# ADF4351_Teensy.net
KiCad netlist of a schematic drawn in EAGLE
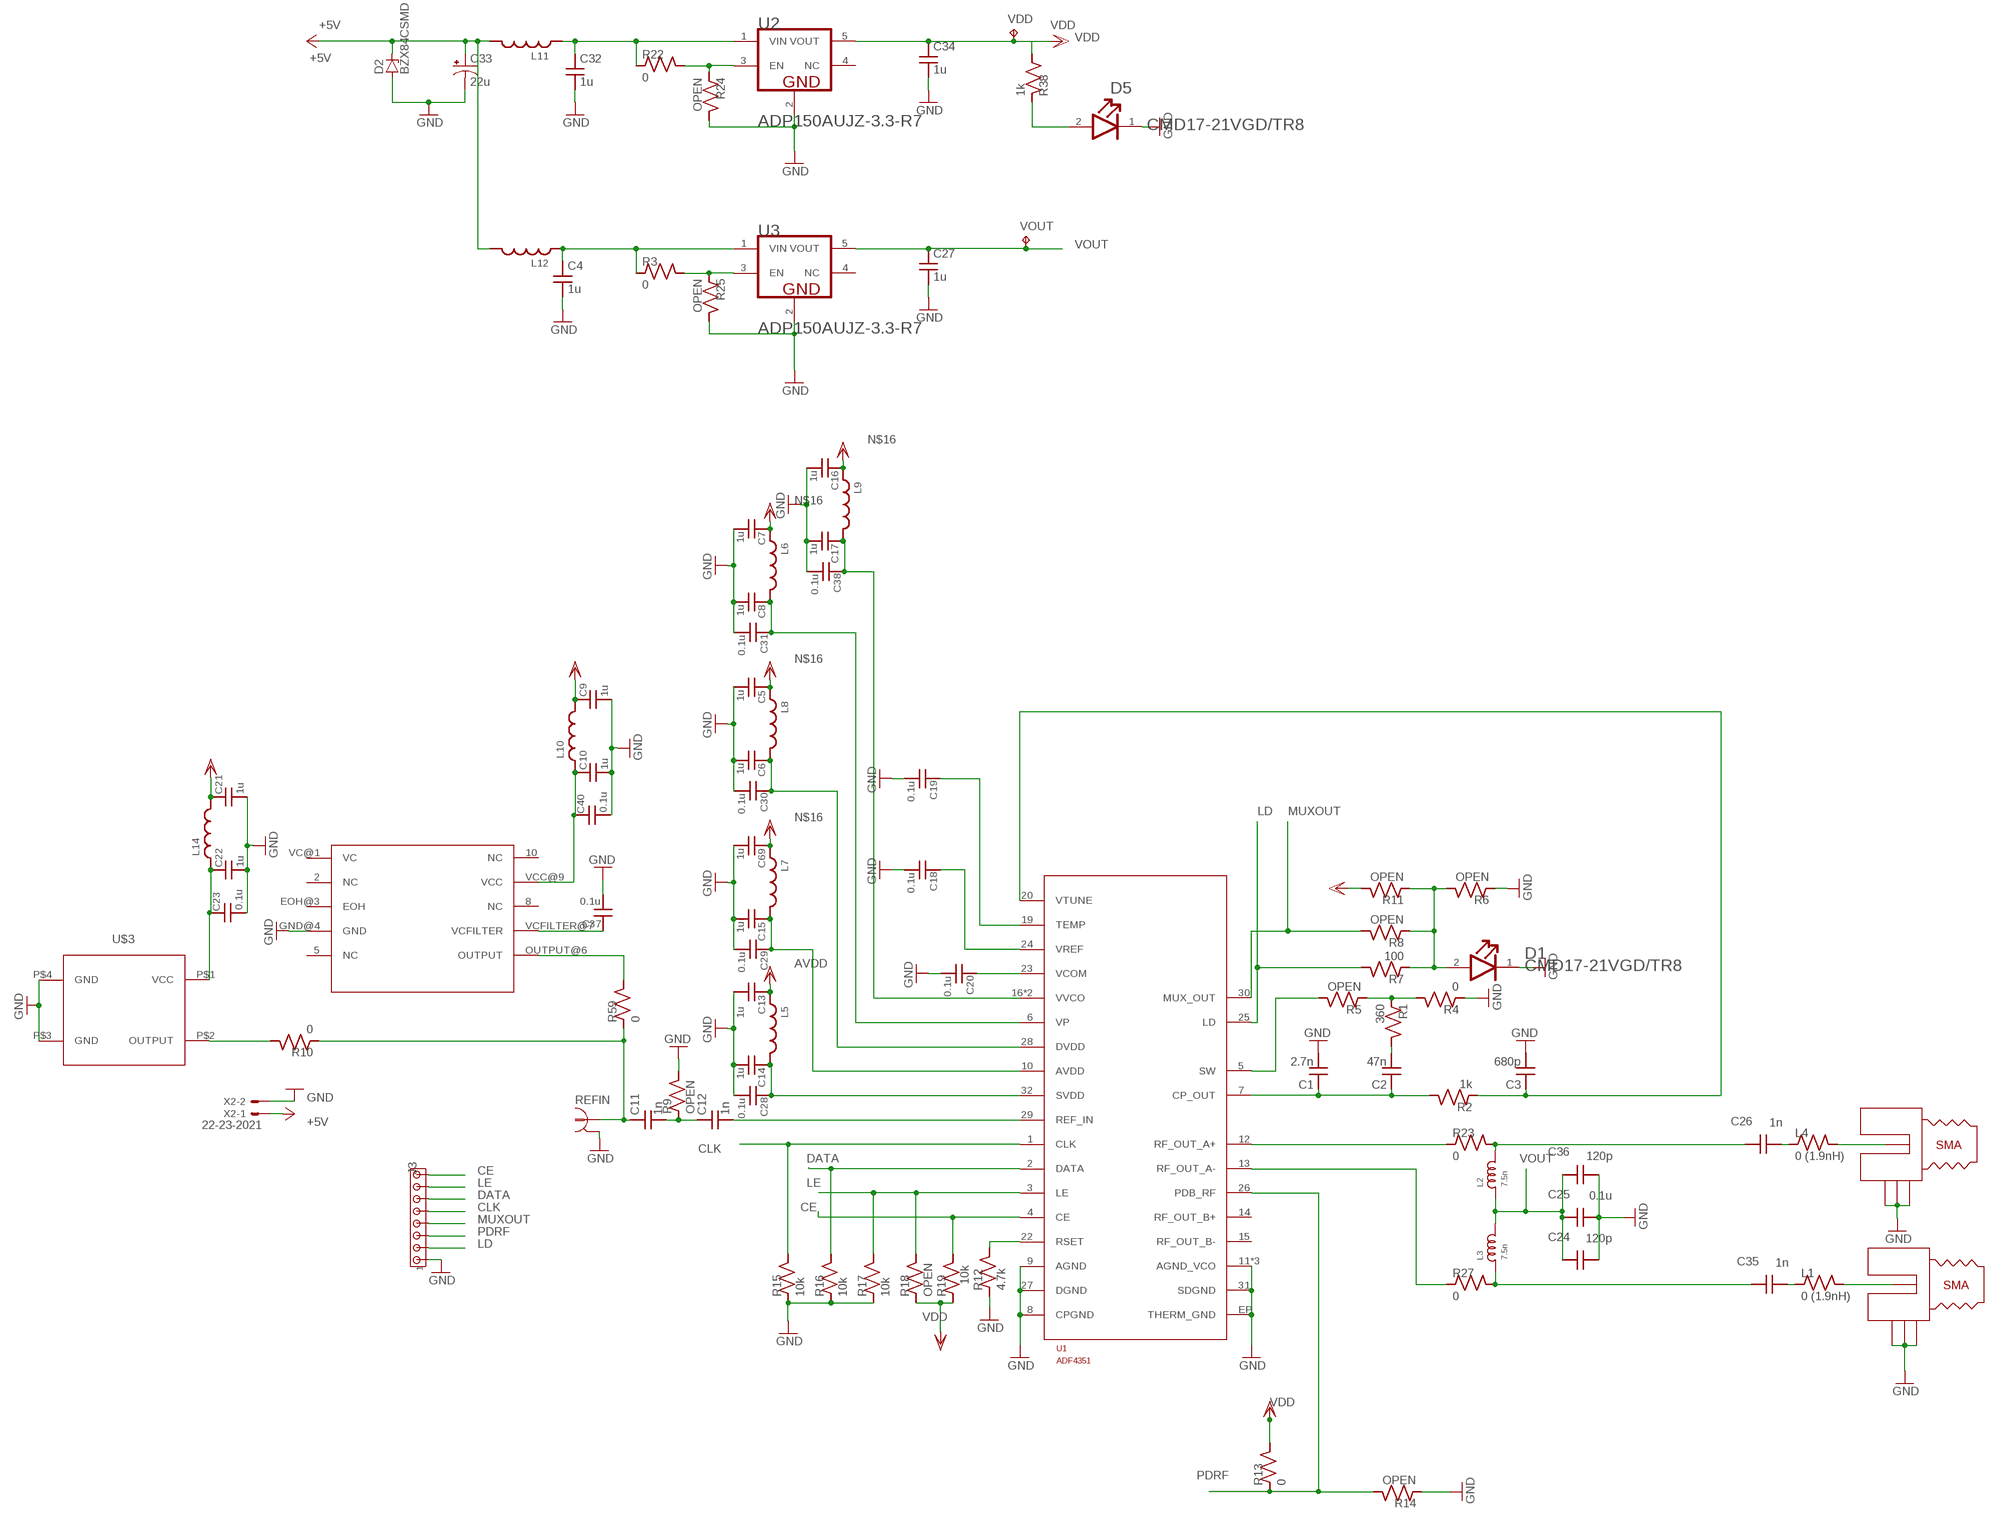
[diagram p0: schematic, sheet 1, part 1 of 2]
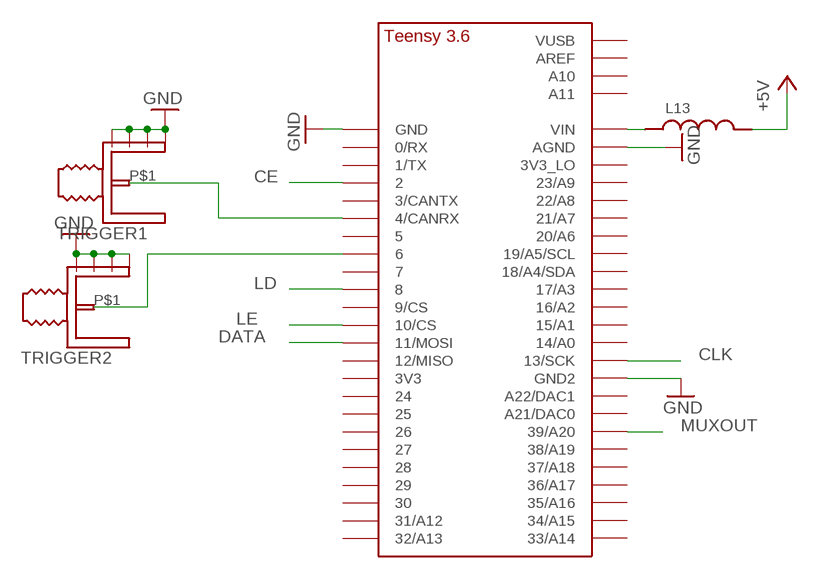
[diagram p1: schematic, sheet 1, part 2 of 2]

(export (version "E")
  (design (tool "Eeschema 10.0.6"))
  (components
    (comp (ref "535L250X2GT5")
      (value "535L250X2GT5")
      (footprint "eagle-import:535L250X2GT5")
      (libsource (lib "eagle-import") (part "535L250X2GT5"))
    )
    (comp (ref "C1")
      (value "2.7n")
      (footprint "eagle-import:C_MLCC_0603")
      (fields
        (field (name "DIGIKEY_PART_NUMBER") "1276-2022-1-ND")
        (field (name "PART_NUMBER") "CL10B272KB8NNNC")
      )
      (libsource (lib "eagle-import") (part "C_MLCC_SMDCMLCC_0603"))
    )
    (comp (ref "C2")
      (value "47n")
      (footprint "eagle-import:C_MLCC_0603")
      (fields
        (field (name "DIGIKEY_PART_NUMBER") "1276-2070-1-ND")
        (field (name "PART_NUMBER") "CL10B473JB8NNNC")
      )
      (libsource (lib "eagle-import") (part "C_MLCC_SMDCMLCC_0603"))
    )
    (comp (ref "C3")
      (value "680p")
      (footprint "eagle-import:C_MLCC_0603")
      (fields
        (field (name "DIGIKEY_PART_NUMBER") "1276-2327-1-ND")
        (field (name "PART_NUMBER") "CL10C681FB8NNNC")
      )
      (libsource (lib "eagle-import") (part "C_MLCC_SMDCMLCC_0603"))
    )
    (comp (ref "C4")
      (value "1u")
      (footprint "eagle-import:C_MLCC_0603")
      (fields
        (field (name "DIGIKEY_PART_NUMBER") "1276-1019-1-ND")
        (field (name "PART_NUMBER") "CL10B105KO8NNNC")
      )
      (libsource (lib "eagle-import") (part "C_MLCC_SMDCMLCC_0603"))
    )
    (comp (ref "C5")
      (value "1u")
      (footprint "eagle-import:C_MLCC_0306")
      (fields
        (field (name "DIGIKEY_PART_NUMBER") "445-13750-1-ND")
        (field (name "PART_NUMBER") "C0816X5R1C105M050AC")
      )
      (libsource (lib "eagle-import") (part "C_MLCC_SMDCMLCC_0306"))
    )
    (comp (ref "C6")
      (value "1u")
      (footprint "eagle-import:C_MLCC_0306")
      (fields
        (field (name "DIGIKEY_PART_NUMBER") "445-13750-1-ND")
        (field (name "PART_NUMBER") "C0816X5R1C105M050AC")
      )
      (libsource (lib "eagle-import") (part "C_MLCC_SMDCMLCC_0306"))
    )
    (comp (ref "C7")
      (value "1u")
      (footprint "eagle-import:C_MLCC_0306")
      (fields
        (field (name "DIGIKEY_PART_NUMBER") "445-13750-1-ND")
        (field (name "PART_NUMBER") "C0816X5R1C105M050AC")
      )
      (libsource (lib "eagle-import") (part "C_MLCC_SMDCMLCC_0306"))
    )
    (comp (ref "C8")
      (value "1u")
      (footprint "eagle-import:C_MLCC_0306")
      (fields
        (field (name "DIGIKEY_PART_NUMBER") "445-13750-1-ND")
        (field (name "PART_NUMBER") "C0816X5R1C105M050AC")
      )
      (libsource (lib "eagle-import") (part "C_MLCC_SMDCMLCC_0306"))
    )
    (comp (ref "C9")
      (value "1u")
      (footprint "eagle-import:C_MLCC_0306")
      (fields
        (field (name "DIGIKEY_PART_NUMBER") "445-13750-1-ND")
        (field (name "PART_NUMBER") "C0816X5R1C105M050AC")
      )
      (libsource (lib "eagle-import") (part "C_MLCC_SMDCMLCC_0306"))
    )
    (comp (ref "C10")
      (value "1u")
      (footprint "eagle-import:C_MLCC_0306")
      (fields
        (field (name "DIGIKEY_PART_NUMBER") "445-13750-1-ND")
        (field (name "PART_NUMBER") "C0816X5R1C105M050AC")
      )
      (libsource (lib "eagle-import") (part "C_MLCC_SMDCMLCC_0306"))
    )
    (comp (ref "C11")
      (value "1n")
      (footprint "eagle-import:C_MLCC_0603")
      (fields
        (field (name "DIGIKEY_PART_NUMBER") "1276-1091-1-ND")
        (field (name "PART_NUMBER") "CL10C102JB8NNNC")
      )
      (libsource (lib "eagle-import") (part "C_MLCC_SMDCMLCC_0603"))
    )
    (comp (ref "C12")
      (value "1n")
      (footprint "eagle-import:C_MLCC_0603")
      (fields
        (field (name "DIGIKEY_PART_NUMBER") "1276-1091-1-ND")
        (field (name "PART_NUMBER") "CL10C102JB8NNNC")
      )
      (libsource (lib "eagle-import") (part "C_MLCC_SMDCMLCC_0603"))
    )
    (comp (ref "C13")
      (value "1u")
      (footprint "eagle-import:C_MLCC_0306")
      (fields
        (field (name "DIGIKEY_PART_NUMBER") "445-13750-1-ND")
        (field (name "PART_NUMBER") "C0816X5R1C105M050AC")
      )
      (libsource (lib "eagle-import") (part "C_MLCC_SMDCMLCC_0306"))
    )
    (comp (ref "C14")
      (value "1u")
      (footprint "eagle-import:C_MLCC_0306")
      (fields
        (field (name "DIGIKEY_PART_NUMBER") "445-13750-1-ND")
        (field (name "PART_NUMBER") "C0816X5R1C105M050AC")
      )
      (libsource (lib "eagle-import") (part "C_MLCC_SMDCMLCC_0306"))
    )
    (comp (ref "C15")
      (value "1u")
      (footprint "eagle-import:C_MLCC_0306")
      (fields
        (field (name "DIGIKEY_PART_NUMBER") "445-13750-1-ND")
        (field (name "PART_NUMBER") "C0816X5R1C105M050AC")
      )
      (libsource (lib "eagle-import") (part "C_MLCC_SMDCMLCC_0306"))
    )
    (comp (ref "C16")
      (value "1u")
      (footprint "eagle-import:C_MLCC_0306")
      (fields
        (field (name "DIGIKEY_PART_NUMBER") "445-13750-1-ND")
        (field (name "PART_NUMBER") "C0816X5R1C105M050AC")
      )
      (libsource (lib "eagle-import") (part "C_MLCC_SMDCMLCC_0306"))
    )
    (comp (ref "C17")
      (value "1u")
      (footprint "eagle-import:C_MLCC_0306")
      (fields
        (field (name "DIGIKEY_PART_NUMBER") "445-13750-1-ND")
        (field (name "PART_NUMBER") "C0816X5R1C105M050AC")
      )
      (libsource (lib "eagle-import") (part "C_MLCC_SMDCMLCC_0306"))
    )
    (comp (ref "C18")
      (value "0.1u")
      (footprint "eagle-import:C_MLCC_0204")
      (fields
        (field (name "DIGIKEY_PART_NUMBER") "587-5137-1-ND")
        (field (name "PART_NUMBER") "LWK105C7104MP-F")
      )
      (libsource (lib "eagle-import") (part "C_MLCC_SMDCMLCC_0204"))
    )
    (comp (ref "C19")
      (value "0.1u")
      (footprint "eagle-import:C_MLCC_0204")
      (fields
        (field (name "DIGIKEY_PART_NUMBER") "587-5137-1-ND")
        (field (name "PART_NUMBER") "LWK105C7104MP-F")
      )
      (libsource (lib "eagle-import") (part "C_MLCC_SMDCMLCC_0204"))
    )
    (comp (ref "C20")
      (value "0.1u")
      (footprint "eagle-import:C_MLCC_0204")
      (fields
        (field (name "DIGIKEY_PART_NUMBER") "587-5137-1-ND")
        (field (name "PART_NUMBER") "LWK105C7104MP-F")
      )
      (libsource (lib "eagle-import") (part "C_MLCC_SMDCMLCC_0204"))
    )
    (comp (ref "C21")
      (value "1u")
      (footprint "eagle-import:C_MLCC_0306")
      (fields
        (field (name "DIGIKEY_PART_NUMBER") "445-13750-1-ND")
        (field (name "PART_NUMBER") "C0816X5R1C105M050AC")
      )
      (libsource (lib "eagle-import") (part "C_MLCC_SMDCMLCC_0306"))
    )
    (comp (ref "C22")
      (value "1u")
      (footprint "eagle-import:C_MLCC_0306")
      (fields
        (field (name "DIGIKEY_PART_NUMBER") "445-13750-1-ND")
        (field (name "PART_NUMBER") "C0816X5R1C105M050AC")
      )
      (libsource (lib "eagle-import") (part "C_MLCC_SMDCMLCC_0306"))
    )
    (comp (ref "C23")
      (value "0.1u")
      (footprint "eagle-import:C_MLCC_0204")
      (fields
        (field (name "DIGIKEY_PART_NUMBER") "587-5137-1-ND")
        (field (name "PART_NUMBER") "LWK105C7104MP-F")
      )
      (libsource (lib "eagle-import") (part "C_MLCC_SMDCMLCC_0204"))
    )
    (comp (ref "C24")
      (value "120p")
      (footprint "eagle-import:C_MLCC_0402")
      (fields
        (field (name "DIGIKEY_PART_NUMBER") "587-3738-1-ND")
        (field (name "PART_NUMBER") "UMK105CG121JVHF")
      )
      (libsource (lib "eagle-import") (part "C_MLCC_SMDCMLCC_0402"))
    )
    (comp (ref "C25")
      (value "0.1u")
      (footprint "eagle-import:C_MLCC_0402")
      (fields
        (field (name "DIGIKEY_PART_NUMBER") "587-1451-1-ND")
        (field (name "PART_NUMBER") "EMK105B7104KV-F")
      )
      (libsource (lib "eagle-import") (part "C_MLCC_SMDCMLCC_0402"))
    )
    (comp (ref "C26")
      (value "1n")
      (footprint "eagle-import:C_MLCC_0402")
      (fields
        (field (name "DIGIKEY_PART_NUMBER") "1276-1635-1-ND")
        (field (name "PART_NUMBER") "CL05C102JB5NNNC")
      )
      (libsource (lib "eagle-import") (part "C_MLCC_SMDCMLCC_0402"))
    )
    (comp (ref "C27")
      (value "1u")
      (footprint "eagle-import:C_MLCC_0603")
      (fields
        (field (name "DIGIKEY_PART_NUMBER") "1276-1019-1-ND")
        (field (name "PART_NUMBER") "CL10B105KO8NNNC")
      )
      (libsource (lib "eagle-import") (part "C_MLCC_SMDCMLCC_0603"))
    )
    (comp (ref "C28")
      (value "0.1u")
      (footprint "eagle-import:C_MLCC_0204")
      (fields
        (field (name "DIGIKEY_PART_NUMBER") "587-5137-1-ND")
        (field (name "PART_NUMBER") "LWK105C7104MP-F")
      )
      (libsource (lib "eagle-import") (part "C_MLCC_SMDCMLCC_0204"))
    )
    (comp (ref "C29")
      (value "0.1u")
      (footprint "eagle-import:C_MLCC_0204")
      (fields
        (field (name "DIGIKEY_PART_NUMBER") "587-5137-1-ND")
        (field (name "PART_NUMBER") "LWK105C7104MP-F")
      )
      (libsource (lib "eagle-import") (part "C_MLCC_SMDCMLCC_0204"))
    )
    (comp (ref "C30")
      (value "0.1u")
      (footprint "eagle-import:C_MLCC_0204")
      (fields
        (field (name "DIGIKEY_PART_NUMBER") "587-5137-1-ND")
        (field (name "PART_NUMBER") "LWK105C7104MP-F")
      )
      (libsource (lib "eagle-import") (part "C_MLCC_SMDCMLCC_0204"))
    )
    (comp (ref "C31")
      (value "0.1u")
      (footprint "eagle-import:C_MLCC_0204")
      (fields
        (field (name "DIGIKEY_PART_NUMBER") "587-5137-1-ND")
        (field (name "PART_NUMBER") "LWK105C7104MP-F")
      )
      (libsource (lib "eagle-import") (part "C_MLCC_SMDCMLCC_0204"))
    )
    (comp (ref "C32")
      (value "1u")
      (footprint "eagle-import:C_MLCC_0603")
      (fields
        (field (name "DIGIKEY_PART_NUMBER") "1276-1019-1-ND")
        (field (name "PART_NUMBER") "CL10B105KO8NNNC")
      )
      (libsource (lib "eagle-import") (part "C_MLCC_SMDCMLCC_0603"))
    )
    (comp (ref "C33")
      (value "22u")
      (footprint "eagle-import:CT7343")
      (fields
        (field (name "DIGIKEY_PART_NUMBER") "478-3923-1-ND")
        (field (name "PART_NUMBER") "TAJD226K020RNJ")
      )
      (libsource (lib "eagle-import") (part "CPOL-USCT7343"))
    )
    (comp (ref "C34")
      (value "1u")
      (footprint "eagle-import:C_MLCC_0603")
      (fields
        (field (name "DIGIKEY_PART_NUMBER") "1276-1019-1-ND")
        (field (name "PART_NUMBER") "CL10B105KO8NNNC")
      )
      (libsource (lib "eagle-import") (part "C_MLCC_SMDCMLCC_0603"))
    )
    (comp (ref "C35")
      (value "1n")
      (footprint "eagle-import:C_MLCC_0402")
      (fields
        (field (name "DIGIKEY_PART_NUMBER") "1276-1635-1-ND")
        (field (name "PART_NUMBER") "CL05C102JB5NNNC")
      )
      (libsource (lib "eagle-import") (part "C_MLCC_SMDCMLCC_0402"))
    )
    (comp (ref "C36")
      (value "120p")
      (footprint "eagle-import:C_MLCC_0402")
      (fields
        (field (name "DIGIKEY_PART_NUMBER") "587-3738-1-ND")
        (field (name "PART_NUMBER") "UMK105CG121JVHF")
      )
      (libsource (lib "eagle-import") (part "C_MLCC_SMDCMLCC_0402"))
    )
    (comp (ref "C37")
      (value "0.1u")
      (footprint "eagle-import:C_MLCC_0204")
      (fields
        (field (name "DIGIKEY_PART_NUMBER") "587-5137-1-ND")
        (field (name "PART_NUMBER") "LWK105C7104MP-F")
      )
      (libsource (lib "eagle-import") (part "C_MLCC_SMDCMLCC_0204"))
    )
    (comp (ref "C38")
      (value "0.1u")
      (footprint "eagle-import:C_MLCC_0204")
      (fields
        (field (name "DIGIKEY_PART_NUMBER") "587-5137-1-ND")
        (field (name "PART_NUMBER") "LWK105C7104MP-F")
      )
      (libsource (lib "eagle-import") (part "C_MLCC_SMDCMLCC_0204"))
    )
    (comp (ref "C40")
      (value "0.1u")
      (footprint "eagle-import:C_MLCC_0204")
      (fields
        (field (name "DIGIKEY_PART_NUMBER") "587-5137-1-ND")
        (field (name "PART_NUMBER") "LWK105C7104MP-F")
      )
      (libsource (lib "eagle-import") (part "C_MLCC_SMDCMLCC_0204"))
    )
    (comp (ref "C69")
      (value "1u")
      (footprint "eagle-import:C_MLCC_0306")
      (fields
        (field (name "DIGIKEY_PART_NUMBER") "445-13750-1-ND")
        (field (name "PART_NUMBER") "C0816X5R1C105M050AC")
      )
      (libsource (lib "eagle-import") (part "C_MLCC_SMDCMLCC_0306"))
    )
    (comp (ref "D1")
      (value "VISUAL_COMMUNICATIONS_CMD17-21VGD-TR8VISUAL_COMMUNICATIONS_CMD17-21VGD-TR8_0_0")
      (footprint "eagle-import:VISUAL_COMMUNICATIONS_CMD17-21VGD-TR8_0")
      (fields
        (field (name "DIGIKEY_PART_NUMBER") "L62505CT-ND")
        (field (name "MF") "Visual Communications")
        (field (name "MOUSER_PART_NUMBER") "606-CMD17-21VGD")
      )
      (libsource (lib "eagle-import") (part "VISUAL_COMMUNICATIONS_CMD17-21VGD-TR8VISUAL_COMMUNICATIONS_CMD17-21VGD-TR8_0_0"))
    )
    (comp (ref "D2")
      (value "BZX84CSMD")
      (footprint "eagle-import:TO236")
      (fields
        (field (name "DIGIKEY_PART_NUMBER") "1727-2942-1-ND")
        (field (name "PART_NUMBER") "BZX84-C6V8,215")
      )
      (libsource (lib "eagle-import") (part "BZX84CSMD"))
    )
    (comp (ref "D5")
      (value "VISUAL_COMMUNICATIONS_CMD17-21VGD-TR8VISUAL_COMMUNICATIONS_CMD17-21VGD-TR8_0_0")
      (footprint "eagle-import:VISUAL_COMMUNICATIONS_CMD17-21VGD-TR8_0")
      (fields
        (field (name "DIGIKEY_PART_NUMBER") "L62505CT-ND")
        (field (name "MF") "Visual Communications")
        (field (name "MOUSER_PART_NUMBER") "606-CMD17-21VGD")
        (field (name "DIGIKEY_PART_NUMBER_1") "L62501CT-ND")
        (field (name "MFG_PACKAGE_IDENT") "CMD17-21VRD/TR8")
        (field (name "MPN") "CMD17-21VRD/TR8")
      )
      (libsource (lib "eagle-import") (part "VISUAL_COMMUNICATIONS_CMD17-21VGD-TR8VISUAL_COMMUNICATIONS_CMD17-21VGD-TR8_0_0"))
    )
    (comp (ref "J1")
      (value "QKDLAB_JOSH_MECHANICAL_JOHNSON_SMA_18GHZ_142-0761-891")
      (footprint "eagle-import:QKDLAB_JOSH_MECHANICAL_JOHNSON_SMA_18GHZ_4-LAYER_142-0761-891")
      (fields (field (name "DIGIKEY_PART_NUMBER") "J802-ND") (field (name "PART_NUMBER") "142-0761-891"))
      (libsource (lib "eagle-import") (part "QKDLAB_JOSH_MECHANICAL_JOHNSON_SMA_18GHZ_142-0761-891"))
    )
    (comp (ref "J2")
      (value "QKDLAB_JOSH_MECHANICAL_JOHNSON_SMA_18GHZ_142-0761-891")
      (footprint "eagle-import:QKDLAB_JOSH_MECHANICAL_JOHNSON_SMA_18GHZ_4-LAYER_142-0761-891")
      (fields (field (name "DIGIKEY_PART_NUMBER") "J802-ND") (field (name "PART_NUMBER") "142-0761-891"))
      (libsource (lib "eagle-import") (part "QKDLAB_JOSH_MECHANICAL_JOHNSON_SMA_18GHZ_142-0761-891"))
    )
    (comp (ref "J3")
      (value "MTA08-100")
      (footprint "eagle-import:10X08MTA")
      (libsource (lib "eagle-import") (part "MTA08-100"))
    )
    (comp (ref "L1")
      (value "0 (1.9nH)")
      (footprint "eagle-import:R_0402")
      (fields
        (field (name "DIGIKEY_PART_NUMBER") "541-1887-1-ND")
        (field (name "PART_NUMBER") "RCG04020000Z0ED")
      )
      (libsource (lib "eagle-import") (part "R_SMDR0402"))
    )
    (comp (ref "L2")
      (value "7.5n")
      (footprint "eagle-import:0402")
      (fields
        (field (name "DIGIKEY_PART_NUMBER") "A102558CT-ND")
        (field (name "PART_NUMBER") "36501E7N5JTDG")
      )
      (libsource (lib "eagle-import") (part "INDUCTOR-0402"))
    )
    (comp (ref "L3")
      (value "7.5n")
      (footprint "eagle-import:0402")
      (fields
        (field (name "DIGIKEY_PART_NUMBER") "A102558CT-ND")
        (field (name "PART_NUMBER") "36501E7N5JTDG")
      )
      (libsource (lib "eagle-import") (part "INDUCTOR-0402"))
    )
    (comp (ref "L4")
      (value "0 (1.9nH)")
      (footprint "eagle-import:R_0402")
      (fields
        (field (name "DIGIKEY_PART_NUMBER") "541-1887-1-ND")
        (field (name "PART_NUMBER") "RCG04020000Z0ED")
      )
      (libsource (lib "eagle-import") (part "R_SMDR0402"))
    )
    (comp (ref "L5")
      (value "L_FERRITE_SMDLFERRITE_0603")
      (footprint "eagle-import:L_FERRITE_0603")
      (fields
        (field (name "DIGIKEY_PART_NUMBER") "490-17350-1-ND")
        (field (name "PART_NUMBER") "BLM18KG102SZ1D")
      )
      (libsource (lib "eagle-import") (part "L_FERRITE_SMDLFERRITE_0603"))
    )
    (comp (ref "L6")
      (value "L_FERRITE_SMDLFERRITE_0603")
      (footprint "eagle-import:L_FERRITE_0603")
      (fields
        (field (name "DIGIKEY_PART_NUMBER") "490-17350-1-ND")
        (field (name "PART_NUMBER") "BLM18KG102SZ1D")
      )
      (libsource (lib "eagle-import") (part "L_FERRITE_SMDLFERRITE_0603"))
    )
    (comp (ref "L7")
      (value "L_FERRITE_SMDLFERRITE_0603")
      (footprint "eagle-import:L_FERRITE_0603")
      (fields
        (field (name "DIGIKEY_PART_NUMBER") "490-17350-1-ND")
        (field (name "PART_NUMBER") "BLM18KG102SZ1D")
      )
      (libsource (lib "eagle-import") (part "L_FERRITE_SMDLFERRITE_0603"))
    )
    (comp (ref "L8")
      (value "L_FERRITE_SMDLFERRITE_0603")
      (footprint "eagle-import:L_FERRITE_0603")
      (fields
        (field (name "DIGIKEY_PART_NUMBER") "490-17350-1-ND")
        (field (name "PART_NUMBER") "BLM18KG102SZ1D")
      )
      (libsource (lib "eagle-import") (part "L_FERRITE_SMDLFERRITE_0603"))
    )
    (comp (ref "L9")
      (value "L_FERRITE_SMDLFERRITE_0603")
      (footprint "eagle-import:L_FERRITE_0603")
      (fields
        (field (name "DIGIKEY_PART_NUMBER") "490-17350-1-ND")
        (field (name "PART_NUMBER") "BLM18KG102SZ1D")
      )
      (libsource (lib "eagle-import") (part "L_FERRITE_SMDLFERRITE_0603"))
    )
    (comp (ref "L10")
      (value "L_FERRITE_SMDLFERRITE_0603")
      (footprint "eagle-import:L_FERRITE_0603")
      (fields
        (field (name "DIGIKEY_PART_NUMBER") "490-17350-1-ND")
        (field (name "PART_NUMBER") "BLM18KG102SZ1D")
      )
      (libsource (lib "eagle-import") (part "L_FERRITE_SMDLFERRITE_0603"))
    )
    (comp (ref "L11")
      (value "L_FERRITE_SMDLFERRITE_0603")
      (footprint "eagle-import:L_FERRITE_0603")
      (fields
        (field (name "DIGIKEY_PART_NUMBER") "490-17350-1-ND")
        (field (name "PART_NUMBER") "BLM18KG102SZ1D")
      )
      (libsource (lib "eagle-import") (part "L_FERRITE_SMDLFERRITE_0603"))
    )
    (comp (ref "L12")
      (value "L_FERRITE_SMDLFERRITE_0603")
      (footprint "eagle-import:L_FERRITE_0603")
      (fields
        (field (name "DIGIKEY_PART_NUMBER") "490-17350-1-ND")
        (field (name "PART_NUMBER") "BLM18KG102SZ1D")
      )
      (libsource (lib "eagle-import") (part "L_FERRITE_SMDLFERRITE_0603"))
    )
    (comp (ref "L13")
      (value "L_FERRITE_SMDLFERRITE_0603")
      (footprint "eagle-import:L_FERRITE_0603")
      (fields
        (field (name "DIGIKEY_PART_NUMBER") "490-17350-1-ND")
        (field (name "PART_NUMBER") "BLM18KG102SZ1D")
      )
      (libsource (lib "eagle-import") (part "L_FERRITE_SMDLFERRITE_0603"))
    )
    (comp (ref "L14")
      (value "L_FERRITE_SMDLFERRITE_0603")
      (footprint "eagle-import:L_FERRITE_0603")
      (fields
        (field (name "DIGIKEY_PART_NUMBER") "490-17350-1-ND")
        (field (name "PART_NUMBER") "BLM18KG102SZ1D")
      )
      (libsource (lib "eagle-import") (part "L_FERRITE_SMDLFERRITE_0603"))
    )
    (comp (ref "R1")
      (value "360")
      (footprint "eagle-import:R_0603")
      (fields (field (name "DIGIKEY_PART_NUMBER") "P360GCT-ND") (field (name "PART_NUMBER") "ERJ-3GEYJ361V"))
      (libsource (lib "eagle-import") (part "R_SMDR0603"))
    )
    (comp (ref "R2")
      (value "1k")
      (footprint "eagle-import:R_0603")
      (fields (field (name "DIGIKEY_PART_NUMBER") "P1.0KDBCT-ND") (field (name "PART_NUMBER") "ERA-3AEB102V"))
      (libsource (lib "eagle-import") (part "R_SMDR0603"))
    )
    (comp (ref "R3")
      (value "0")
      (footprint "eagle-import:R_0603")
      (fields
        (field (name "DIGIKEY_PART_NUMBER") "541-4012-1-ND")
        (field (name "PART_NUMBER") "CRCW06030000Z0EAC")
      )
      (libsource (lib "eagle-import") (part "R_SMDR0603"))
    )
    (comp (ref "R4")
      (value "0")
      (footprint "eagle-import:R_0603")
      (fields
        (field (name "DIGIKEY_PART_NUMBER") "541-4012-1-ND")
        (field (name "PART_NUMBER") "CRCW06030000Z0EAC")
      )
      (libsource (lib "eagle-import") (part "R_SMDR0603"))
    )
    (comp (ref "R5")
      (value "OPEN")
      (footprint "eagle-import:R_0603")
      (libsource (lib "eagle-import") (part "R_SMDR0603"))
    )
    (comp (ref "R6")
      (value "OPEN")
      (footprint "eagle-import:R_0603")
      (libsource (lib "eagle-import") (part "R_SMDR0603"))
    )
    (comp (ref "R7")
      (value "100")
      (footprint "eagle-import:R_0603")
      (fields
        (field (name "DIGIKEY_PART_NUMBER") "541-3951-1-ND")
        (field (name "PART_NUMBER") "CRCW0603100RFKEAC")
      )
      (libsource (lib "eagle-import") (part "R_SMDR0603"))
    )
    (comp (ref "R8")
      (value "OPEN")
      (footprint "eagle-import:R_0603")
      (libsource (lib "eagle-import") (part "R_SMDR0603"))
    )
    (comp (ref "R9")
      (value "OPEN")
      (footprint "eagle-import:R_0603")
      (fields
        (field (name "DIGIKEY_PART_NUMBER") "MCT0603-10.0K-CFCT-ND")
        (field (name "PART_NUMBER") "MCT06030C1002FP500")
      )
      (libsource (lib "eagle-import") (part "R_SMDR0603"))
    )
    (comp (ref "R10")
      (value "0")
      (footprint "eagle-import:R_0603")
      (fields
        (field (name "DIGIKEY_PART_NUMBER") "541-4012-1-ND")
        (field (name "PART_NUMBER") "CRCW06030000Z0EAC")
      )
      (libsource (lib "eagle-import") (part "R_SMDR0603"))
    )
    (comp (ref "R11")
      (value "OPEN")
      (footprint "eagle-import:R_0603")
      (libsource (lib "eagle-import") (part "R_SMDR0603"))
    )
    (comp (ref "R12")
      (value "4.7k")
      (footprint "eagle-import:R_0603")
      (fields
        (field (name "DIGIKEY_PART_NUMBER") "541-3993-1-ND")
        (field (name "PART_NUMBER") "CRCW06034K70JNEAC")
      )
      (libsource (lib "eagle-import") (part "R_SMDR0603"))
    )
    (comp (ref "R13")
      (value "0")
      (footprint "eagle-import:R_0603")
      (fields
        (field (name "DIGIKEY_PART_NUMBER") "541-4012-1-ND")
        (field (name "PART_NUMBER") "CRCW06030000Z0EAC")
      )
      (libsource (lib "eagle-import") (part "R_SMDR0603"))
    )
    (comp (ref "R14")
      (value "OPEN")
      (footprint "eagle-import:R_0603")
      (libsource (lib "eagle-import") (part "R_SMDR0603"))
    )
    (comp (ref "R15")
      (value "10k")
      (footprint "eagle-import:R_0603")
      (fields
        (field (name "DIGIKEY_PART_NUMBER") "MCT0603-10.0K-CFCT-ND")
        (field (name "PART_NUMBER") "MCT06030C1002FP500")
      )
      (libsource (lib "eagle-import") (part "R_SMDR0603"))
    )
    (comp (ref "R16")
      (value "10k")
      (footprint "eagle-import:R_0603")
      (fields
        (field (name "DIGIKEY_PART_NUMBER") "MCT0603-10.0K-CFCT-ND")
        (field (name "PART_NUMBER") "MCT06030C1002FP500")
      )
      (libsource (lib "eagle-import") (part "R_SMDR0603"))
    )
    (comp (ref "R17")
      (value "10k")
      (footprint "eagle-import:R_0603")
      (fields
        (field (name "DIGIKEY_PART_NUMBER") "MCT0603-10.0K-CFCT-ND")
        (field (name "PART_NUMBER") "MCT06030C1002FP500")
      )
      (libsource (lib "eagle-import") (part "R_SMDR0603"))
    )
    (comp (ref "R18")
      (value "OPEN")
      (footprint "eagle-import:R_0603")
      (fields
        (field (name "DIGIKEY_PART_NUMBER") "MCT0603-10.0K-CFCT-ND")
        (field (name "PART_NUMBER") "MCT06030C1002FP500")
      )
      (libsource (lib "eagle-import") (part "R_SMDR0603"))
    )
    (comp (ref "R19")
      (value "10k")
      (footprint "eagle-import:R_0603")
      (fields
        (field (name "DIGIKEY_PART_NUMBER") "MCT0603-10.0K-CFCT-ND")
        (field (name "PART_NUMBER") "MCT06030C1002FP500")
      )
      (libsource (lib "eagle-import") (part "R_SMDR0603"))
    )
    (comp (ref "R22")
      (value "0")
      (footprint "eagle-import:R_0603")
      (fields
        (field (name "DIGIKEY_PART_NUMBER") "541-4012-1-ND")
        (field (name "PART_NUMBER") "CRCW06030000Z0EAC")
      )
      (libsource (lib "eagle-import") (part "R_SMDR0603"))
    )
    (comp (ref "R23")
      (value "0")
      (footprint "eagle-import:R_0402")
      (fields
        (field (name "DIGIKEY_PART_NUMBER") "541-1887-1-ND")
        (field (name "PART_NUMBER") "RCG04020000Z0ED")
      )
      (libsource (lib "eagle-import") (part "R_SMDR0402"))
    )
    (comp (ref "R24")
      (value "OPEN")
      (footprint "eagle-import:R_0603")
      (libsource (lib "eagle-import") (part "R_SMDR0603"))
    )
    (comp (ref "R25")
      (value "OPEN")
      (footprint "eagle-import:R_0603")
      (libsource (lib "eagle-import") (part "R_SMDR0603"))
    )
    (comp (ref "R27")
      (value "0")
      (footprint "eagle-import:R_0402")
      (fields
        (field (name "DIGIKEY_PART_NUMBER") "541-1887-1-ND")
        (field (name "PART_NUMBER") "RCG04020000Z0ED")
      )
      (libsource (lib "eagle-import") (part "R_SMDR0402"))
    )
    (comp (ref "R38")
      (value "1k")
      (footprint "eagle-import:R_0603")
      (fields (field (name "DIGIKEY_PART_NUMBER") "P1.0KDBCT-ND") (field (name "PART_NUMBER") "ERA-3AEB102V"))
      (libsource (lib "eagle-import") (part "R_SMDR0603"))
    )
    (comp (ref "R59")
      (value "0")
      (footprint "eagle-import:R_0603")
      (fields
        (field (name "DIGIKEY_PART_NUMBER") "541-4012-1-ND")
        (field (name "PART_NUMBER") "CRCW06030000Z0EAC")
      )
      (libsource (lib "eagle-import") (part "R_SMDR0603"))
    )
    (comp (ref "REFIN")
      (value "SMA_CONNECTOR")
      (footprint "eagle-import:QKDLAB_JOSH_MECHANICAL_JOHNSON_SMA_EDGE_LAUNCH_142-0701-851")
      (fields (field (name "DIGIKEY_PART_NUMBER") "J658-ND") (field (name "PART_NUMBER") "142-0701-851"))
      (libsource (lib "eagle-import") (part "SMA_CONNECTOR"))
    )
    (comp (ref "TRIGGER1")
      (value "JOHNSON_SMA_EDGE_LAUNCH_142-0701-851")
      (footprint "eagle-import:JOHNSON_SMA_EDGE_LAUNCH_142-0701-851")
      (libsource (lib "eagle-import") (part "JOHNSON_SMA_EDGE_LAUNCH_142-0701-851"))
    )
    (comp (ref "TRIGGER2")
      (value "JOHNSON_SMA_EDGE_LAUNCH_142-0701-851")
      (footprint "eagle-import:JOHNSON_SMA_EDGE_LAUNCH_142-0701-851")
      (libsource (lib "eagle-import") (part "JOHNSON_SMA_EDGE_LAUNCH_142-0701-851"))
    )
    (comp (ref "U$1")
      (value "TEENSY_3.5/3.6_BASIC")
      (footprint "eagle-import:TEENSY_3.5_3.6_BASIC")
      (libsource (lib "eagle-import") (part "TEENSY_3.5/3.6_BASIC"))
    )
    (comp (ref "U$3")
      (value "XNCLH25M000THJA0P0")
      (footprint "eagle-import:XNCLH25M000THJA0P0")
      (libsource (lib "eagle-import") (part "XNCLH25M000THJA0P0"))
    )
    (comp (ref "U1")
      (value "ADF4351")
      (footprint "eagle-import:ADF4351")
      (fields (field (name "MF") "Analog Devices"))
      (libsource (lib "eagle-import") (part "ADF4351"))
    )
    (comp (ref "U2")
      (value "ANALOG_DEVICES_ADP150AUJZ-3.3-R7ANALOG_DEVICES_ADP150AUJZ-3.3-R7_0_2")
      (footprint "eagle-import:ANALOG_DEVICES_ADP150AUJZ-3.3-R7_2")
      (fields (field (name "MF") "Analog Devices") (field (name "MPN") "ADP150AUJZ-3.3-R7"))
      (libsource (lib "eagle-import") (part "ANALOG_DEVICES_ADP150AUJZ-3.3-R7ANALOG_DEVICES_ADP150AUJZ-3.3-R7_0_2"))
    )
    (comp (ref "U3")
      (value "ANALOG_DEVICES_ADP150AUJZ-3.3-R7ANALOG_DEVICES_ADP150AUJZ-3.3-R7_0_2")
      (footprint "eagle-import:ANALOG_DEVICES_ADP150AUJZ-3.3-R7_2")
      (fields (field (name "MF") "Analog Devices") (field (name "MPN") "ADP150AUJZ-3.3-R7"))
      (libsource (lib "eagle-import") (part "ANALOG_DEVICES_ADP150AUJZ-3.3-R7ANALOG_DEVICES_ADP150AUJZ-3.3-R7_0_2"))
    )
    (comp (ref "VDD")
      (value "TPB1,27")
      (footprint "eagle-import:B1,27")
      (libsource (lib "eagle-import") (part "TPB1,27"))
    )
    (comp (ref "VOUT")
      (value "TPB1,27")
      (footprint "eagle-import:B1,27")
      (libsource (lib "eagle-import") (part "TPB1,27"))
    )
    (comp (ref "X2")
      (value "22-23-2021")
      (footprint "eagle-import:22-23-2021")
      (fields (field (name "MF") "MOLEX"))
      (libsource (lib "eagle-import") (part "22-23-2021"))
    )
  )
  (nets
    (net (code "1") (name "+5V") (class "Default")
      (node (ref "C33") (pin "+") (pinfunction "+_+") (pintype "passive"))
      (node (ref "D2") (pin "C") (pinfunction "C_C") (pintype "passive"))
      (node (ref "L11") (pin "P$2") (pinfunction "2_P$2") (pintype "passive"))
      (node (ref "L12") (pin "P$2") (pinfunction "2_P$2") (pintype "passive"))
      (node (ref "L13") (pin "P$2") (pinfunction "2_P$2") (pintype "passive"))
      (node (ref "X2") (pin "1") (pinfunction "S_1") (pintype "passive"))
    )
    (net (code "2") (name "/AVDD") (class "Default")
      (node (ref "C15") (pin "P$1") (pinfunction "1_P$1") (pintype "passive"))
      (node (ref "C29") (pin "P$1") (pinfunction "1_P$1") (pintype "passive"))
      (node (ref "L7") (pin "P$2") (pinfunction "2_P$2") (pintype "passive"))
      (node (ref "U1") (pin "10") (pinfunction "AVDD_10") (pintype "bidirectional"))
    )
    (net (code "3") (name "/CE") (class "Default")
      (node (ref "J3") (pin "8") (pinfunction "8_8") (pintype "passive"))
      (node (ref "R19") (pin "P$2") (pinfunction "2_P$2") (pintype "passive"))
      (node (ref "U$1") (pin "2") (pinfunction "2_2") (pintype "bidirectional"))
      (node (ref "U1") (pin "4") (pinfunction "CE_4") (pintype "bidirectional"))
    )
    (net (code "4") (name "/CLK") (class "Default")
      (node (ref "J3") (pin "5") (pinfunction "5_5") (pintype "passive"))
      (node (ref "R15") (pin "P$2") (pinfunction "2_P$2") (pintype "passive"))
      (node (ref "U$1") (pin "13/SCK") (pinfunction "13/SCK_13/SCK") (pintype "bidirectional"))
      (node (ref "U1") (pin "1") (pinfunction "CLK_1") (pintype "bidirectional"))
    )
    (net (code "5") (name "/DATA") (class "Default")
      (node (ref "J3") (pin "6") (pinfunction "6_6") (pintype "passive"))
      (node (ref "R16") (pin "P$2") (pinfunction "2_P$2") (pintype "passive"))
      (node (ref "U$1") (pin "11/MOSI") (pinfunction "11/MOSI_11/MOSI") (pintype "bidirectional"))
      (node (ref "U1") (pin "2") (pinfunction "DATA_2") (pintype "bidirectional"))
    )
    (net (code "6") (name "/LD") (class "Default")
      (node (ref "J3") (pin "2") (pinfunction "2_2") (pintype "passive"))
      (node (ref "R7") (pin "P$2") (pinfunction "2_P$2") (pintype "passive"))
      (node (ref "U$1") (pin "8") (pinfunction "8_8") (pintype "bidirectional"))
      (node (ref "U1") (pin "25") (pinfunction "LD_25") (pintype "bidirectional"))
    )
    (net (code "7") (name "/LE") (class "Default")
      (node (ref "J3") (pin "7") (pinfunction "7_7") (pintype "passive"))
      (node (ref "R17") (pin "P$2") (pinfunction "2_P$2") (pintype "passive"))
      (node (ref "R18") (pin "P$2") (pinfunction "2_P$2") (pintype "passive"))
      (node (ref "U$1") (pin "10/CS") (pinfunction "10/CS_10/CS") (pintype "bidirectional"))
      (node (ref "U1") (pin "3") (pinfunction "LE_3") (pintype "bidirectional"))
    )
    (net (code "8") (name "/MUXOUT") (class "Default")
      (node (ref "J3") (pin "4") (pinfunction "4_4") (pintype "passive"))
      (node (ref "R8") (pin "P$2") (pinfunction "2_P$2") (pintype "passive"))
      (node (ref "U$1") (pin "39/A20") (pinfunction "39/A20_39/A20") (pintype "bidirectional"))
      (node (ref "U1") (pin "30") (pinfunction "MUX_OUT_30") (pintype "bidirectional"))
    )
    (net (code "10") (name "/PDRF") (class "Default")
      (node (ref "J3") (pin "3") (pinfunction "3_3") (pintype "passive"))
      (node (ref "R13") (pin "P$1") (pinfunction "1_P$1") (pintype "passive"))
      (node (ref "R14") (pin "P$2") (pinfunction "2_P$2") (pintype "passive"))
      (node (ref "U1") (pin "26") (pinfunction "PDB_RF_26") (pintype "bidirectional"))
    )
    (net (code "11") (name "/VOUT") (class "Default")
      (node (ref "C24") (pin "P$1") (pinfunction "1_P$1") (pintype "passive"))
      (node (ref "C25") (pin "P$1") (pinfunction "1_P$1") (pintype "passive"))
      (node (ref "C27") (pin "P$1") (pinfunction "1_P$1") (pintype "passive"))
      (node (ref "C36") (pin "P$1") (pinfunction "1_P$1") (pintype "passive"))
      (node (ref "L2") (pin "1") (pinfunction "P$1_1") (pintype "passive"))
      (node (ref "L3") (pin "2") (pinfunction "P$2_2") (pintype "passive"))
      (node (ref "U3") (pin "5") (pinfunction "VOUT_5") (pintype "power_in"))
      (node (ref "VOUT") (pin "TP") (pinfunction "TP_TP") (pintype "input"))
    )
    (net (code "12") (name "GND") (class "Default")
      (node (ref "535L250X2GT5") (pin "GND@4") (pinfunction "GND_GND@4") (pintype "bidirectional"))
      (node (ref "C1") (pin "P$2") (pinfunction "2_P$2") (pintype "passive"))
      (node (ref "C10") (pin "P$2") (pinfunction "2_P$2") (pintype "passive"))
      (node (ref "C13") (pin "P$2") (pinfunction "2_P$2") (pintype "passive"))
      (node (ref "C14") (pin "P$2") (pinfunction "2_P$2") (pintype "passive"))
      (node (ref "C15") (pin "P$2") (pinfunction "2_P$2") (pintype "passive"))
      (node (ref "C16") (pin "P$2") (pinfunction "2_P$2") (pintype "passive"))
      (node (ref "C17") (pin "P$2") (pinfunction "2_P$2") (pintype "passive"))
      (node (ref "C18") (pin "P$2") (pinfunction "2_P$2") (pintype "passive"))
      (node (ref "C19") (pin "P$2") (pinfunction "2_P$2") (pintype "passive"))
      (node (ref "C20") (pin "P$2") (pinfunction "2_P$2") (pintype "passive"))
      (node (ref "C21") (pin "P$2") (pinfunction "2_P$2") (pintype "passive"))
      (node (ref "C22") (pin "P$2") (pinfunction "2_P$2") (pintype "passive"))
      (node (ref "C23") (pin "P$2") (pinfunction "2_P$2") (pintype "passive"))
      (node (ref "C24") (pin "P$2") (pinfunction "2_P$2") (pintype "passive"))
      (node (ref "C25") (pin "P$2") (pinfunction "2_P$2") (pintype "passive"))
      (node (ref "C27") (pin "P$2") (pinfunction "2_P$2") (pintype "passive"))
      (node (ref "C28") (pin "P$2") (pinfunction "2_P$2") (pintype "passive"))
      (node (ref "C29") (pin "P$2") (pinfunction "2_P$2") (pintype "passive"))
      (node (ref "C3") (pin "P$2") (pinfunction "2_P$2") (pintype "passive"))
      (node (ref "C30") (pin "P$2") (pinfunction "2_P$2") (pintype "passive"))
      (node (ref "C31") (pin "P$2") (pinfunction "2_P$2") (pintype "passive"))
      (node (ref "C32") (pin "P$2") (pinfunction "2_P$2") (pintype "passive"))
      (node (ref "C33") (pin "-") (pinfunction "-_-") (pintype "passive"))
      (node (ref "C34") (pin "P$2") (pinfunction "2_P$2") (pintype "passive"))
      (node (ref "C36") (pin "P$2") (pinfunction "2_P$2") (pintype "passive"))
      (node (ref "C37") (pin "P$2") (pinfunction "2_P$2") (pintype "passive"))
      (node (ref "C38") (pin "P$2") (pinfunction "2_P$2") (pintype "passive"))
      (node (ref "C4") (pin "P$2") (pinfunction "2_P$2") (pintype "passive"))
      (node (ref "C40") (pin "P$2") (pinfunction "2_P$2") (pintype "passive"))
      (node (ref "C5") (pin "P$2") (pinfunction "2_P$2") (pintype "passive"))
      (node (ref "C6") (pin "P$2") (pinfunction "2_P$2") (pintype "passive"))
      (node (ref "C69") (pin "P$2") (pinfunction "2_P$2") (pintype "passive"))
      (node (ref "C7") (pin "P$2") (pinfunction "2_P$2") (pintype "passive"))
      (node (ref "C8") (pin "P$2") (pinfunction "2_P$2") (pintype "passive"))
      (node (ref "C9") (pin "P$2") (pinfunction "2_P$2") (pintype "passive"))
      (node (ref "D1") (pin "1") (pinfunction "CATHODE_1") (pintype "passive"))
      (node (ref "D2") (pin "A") (pinfunction "A_A") (pintype "passive"))
      (node (ref "D5") (pin "1") (pinfunction "CATHODE_1") (pintype "passive"))
      (node (ref "J1") (pin "P$2") (pinfunction "GND_P$2") (pintype "bidirectional"))
      (node (ref "J1") (pin "P$3") (pinfunction "GND_P$3") (pintype "bidirectional"))
      (node (ref "J1") (pin "P$4") (pinfunction "GND_P$4") (pintype "bidirectional"))
      (node (ref "J2") (pin "P$2") (pinfunction "GND_P$2") (pintype "bidirectional"))
      (node (ref "J2") (pin "P$3") (pinfunction "GND_P$3") (pintype "bidirectional"))
      (node (ref "J2") (pin "P$4") (pinfunction "GND_P$4") (pintype "bidirectional"))
      (node (ref "J3") (pin "1") (pinfunction "1_1") (pintype "passive"))
      (node (ref "R12") (pin "P$1") (pinfunction "1_P$1") (pintype "passive"))
      (node (ref "R14") (pin "P$1") (pinfunction "1_P$1") (pintype "passive"))
      (node (ref "R15") (pin "P$1") (pinfunction "1_P$1") (pintype "passive"))
      (node (ref "R16") (pin "P$1") (pinfunction "1_P$1") (pintype "passive"))
      (node (ref "R17") (pin "P$1") (pinfunction "1_P$1") (pintype "passive"))
      (node (ref "R24") (pin "P$2") (pinfunction "2_P$2") (pintype "passive"))
      (node (ref "R25") (pin "P$2") (pinfunction "2_P$2") (pintype "passive"))
      (node (ref "R4") (pin "P$1") (pinfunction "1_P$1") (pintype "passive"))
      (node (ref "R6") (pin "P$1") (pinfunction "1_P$1") (pintype "passive"))
      (node (ref "R9") (pin "P$2") (pinfunction "2_P$2") (pintype "passive"))
      (node (ref "REFIN") (pin "P$2") (pinfunction "2_P$2") (pintype "passive"))
      (node (ref "REFIN") (pin "P$3") (pinfunction "2_P$3") (pintype "passive"))
      (node (ref "REFIN") (pin "P$4") (pinfunction "2_P$4") (pintype "passive"))
      (node (ref "REFIN") (pin "P$5") (pinfunction "2_P$5") (pintype "passive"))
      (node (ref "TRIGGER1") (pin "P$2") (pinfunction "GND1_P$2") (pintype "bidirectional"))
      (node (ref "TRIGGER1") (pin "P$3") (pinfunction "GND_P$3") (pintype "bidirectional"))
      (node (ref "TRIGGER1") (pin "P$4") (pinfunction "GND2_P$4") (pintype "bidirectional"))
      (node (ref "TRIGGER1") (pin "P$5") (pinfunction "GND3_P$5") (pintype "bidirectional"))
      (node (ref "TRIGGER2") (pin "P$2") (pinfunction "GND1_P$2") (pintype "bidirectional"))
      (node (ref "TRIGGER2") (pin "P$3") (pinfunction "GND_P$3") (pintype "bidirectional"))
      (node (ref "TRIGGER2") (pin "P$4") (pinfunction "GND2_P$4") (pintype "bidirectional"))
      (node (ref "TRIGGER2") (pin "P$5") (pinfunction "GND3_P$5") (pintype "bidirectional"))
      (node (ref "U$1") (pin "AGND") (pinfunction "AGND_AGND") (pintype "bidirectional"))
      (node (ref "U$1") (pin "GND") (pinfunction "GND_GND") (pintype "bidirectional"))
      (node (ref "U$1") (pin "GND2") (pinfunction "GND2_GND2") (pintype "bidirectional"))
      (node (ref "U$3") (pin "P$3") (pinfunction "GND_P$3") (pintype "bidirectional"))
      (node (ref "U$3") (pin "P$4") (pinfunction "GND_P$4") (pintype "bidirectional"))
      (node (ref "U1") (pin "11") (pinfunction "AGND_VCO_11") (pintype "bidirectional"))
      (node (ref "U1") (pin "18") (pinfunction "AGND_VCO_18") (pintype "bidirectional"))
      (node (ref "U1") (pin "21") (pinfunction "AGND_VCO_21") (pintype "bidirectional"))
      (node (ref "U1") (pin "27") (pinfunction "DGND_27") (pintype "bidirectional"))
      (node (ref "U1") (pin "31") (pinfunction "SDGND_31") (pintype "bidirectional"))
      (node (ref "U1") (pin "8") (pinfunction "CPGND_8") (pintype "bidirectional"))
      (node (ref "U1") (pin "9") (pinfunction "AGND_9") (pintype "bidirectional"))
      (node (ref "U1") (pin "EP") (pinfunction "THERM_GND_EP") (pintype "bidirectional"))
      (node (ref "U2") (pin "2") (pinfunction "GND_2") (pintype "power_in"))
      (node (ref "U3") (pin "2") (pinfunction "GND_2") (pintype "power_in"))
      (node (ref "X2") (pin "2") (pinfunction "S_2") (pintype "passive"))
    )
    (net (code "13") (name "Net-(535L250X2GT5-OUTPUT)") (class "Default")
      (node (ref "535L250X2GT5") (pin "OUTPUT@6") (pinfunction "OUTPUT_OUTPUT@6") (pintype "bidirectional"))
      (node (ref "R59") (pin "P$2") (pinfunction "2_P$2") (pintype "passive"))
    )
    (net (code "14") (name "Net-(535L250X2GT5-VCC)") (class "Default")
      (node (ref "535L250X2GT5") (pin "VCC@9") (pinfunction "VCC_VCC@9") (pintype "bidirectional"))
      (node (ref "C10") (pin "P$1") (pinfunction "1_P$1") (pintype "passive"))
      (node (ref "C40") (pin "P$1") (pinfunction "1_P$1") (pintype "passive"))
      (node (ref "L10") (pin "P$1") (pinfunction "1_P$1") (pintype "passive"))
    )
    (net (code "15") (name "Net-(535L250X2GT5-VCFILTER)") (class "Default")
      (node (ref "535L250X2GT5") (pin "VCFILTER@7") (pinfunction "VCFILTER_VCFILTER@7") (pintype "bidirectional"))
      (node (ref "C37") (pin "P$1") (pinfunction "1_P$1") (pintype "passive"))
    )
    (net (code "16") (name "Net-(C1-1)") (class "Default")
      (node (ref "C1") (pin "P$1") (pinfunction "1_P$1") (pintype "passive"))
      (node (ref "C2") (pin "P$1") (pinfunction "1_P$1") (pintype "passive"))
      (node (ref "R2") (pin "P$2") (pinfunction "2_P$2") (pintype "passive"))
      (node (ref "U1") (pin "7") (pinfunction "CP_OUT_7") (pintype "bidirectional"))
    )
    (net (code "17") (name "Net-(C2-2)") (class "Default")
      (node (ref "C2") (pin "P$2") (pinfunction "2_P$2") (pintype "passive"))
      (node (ref "R1") (pin "P$2") (pinfunction "2_P$2") (pintype "passive"))
    )
    (net (code "18") (name "Net-(C3-1)") (class "Default")
      (node (ref "C3") (pin "P$1") (pinfunction "1_P$1") (pintype "passive"))
      (node (ref "R2") (pin "P$1") (pinfunction "1_P$1") (pintype "passive"))
      (node (ref "U1") (pin "20") (pinfunction "VTUNE_20") (pintype "bidirectional"))
    )
    (net (code "19") (name "Net-(C4-1)") (class "Default")
      (node (ref "C4") (pin "P$1") (pinfunction "1_P$1") (pintype "passive"))
      (node (ref "L12") (pin "P$1") (pinfunction "1_P$1") (pintype "passive"))
      (node (ref "R3") (pin "P$1") (pinfunction "1_P$1") (pintype "passive"))
      (node (ref "U3") (pin "1") (pinfunction "VIN_1") (pintype "power_in"))
    )
    (net (code "20") (name "Net-(C11-1)") (class "Default")
      (node (ref "C11") (pin "P$1") (pinfunction "1_P$1") (pintype "passive"))
      (node (ref "R10") (pin "P$1") (pinfunction "1_P$1") (pintype "passive"))
      (node (ref "R59") (pin "P$1") (pinfunction "1_P$1") (pintype "passive"))
      (node (ref "REFIN") (pin "P$1") (pinfunction "1_P$1") (pintype "passive"))
    )
    (net (code "21") (name "Net-(C11-2)") (class "Default")
      (node (ref "C11") (pin "P$2") (pinfunction "2_P$2") (pintype "passive"))
      (node (ref "C12") (pin "P$1") (pinfunction "1_P$1") (pintype "passive"))
      (node (ref "R9") (pin "P$1") (pinfunction "1_P$1") (pintype "passive"))
    )
    (net (code "22") (name "Net-(C12-2)") (class "Default")
      (node (ref "C12") (pin "P$2") (pinfunction "2_P$2") (pintype "passive"))
      (node (ref "U1") (pin "29") (pinfunction "REF_IN_29") (pintype "bidirectional"))
    )
    (net (code "23") (name "Net-(C14-1)") (class "Default")
      (node (ref "C14") (pin "P$1") (pinfunction "1_P$1") (pintype "passive"))
      (node (ref "C28") (pin "P$1") (pinfunction "1_P$1") (pintype "passive"))
      (node (ref "L5") (pin "P$2") (pinfunction "2_P$2") (pintype "passive"))
      (node (ref "U1") (pin "32") (pinfunction "SVDD_32") (pintype "bidirectional"))
    )
    (net (code "24") (name "Net-(C17-1)") (class "Default")
      (node (ref "C17") (pin "P$1") (pinfunction "1_P$1") (pintype "passive"))
      (node (ref "C38") (pin "P$1") (pinfunction "1_P$1") (pintype "passive"))
      (node (ref "L9") (pin "P$2") (pinfunction "2_P$2") (pintype "passive"))
      (node (ref "U1") (pin "16") (pinfunction "VVCO_16") (pintype "bidirectional"))
      (node (ref "U1") (pin "17") (pinfunction "VVCO_17") (pintype "bidirectional"))
    )
    (net (code "25") (name "Net-(C18-1)") (class "Default")
      (node (ref "C18") (pin "P$1") (pinfunction "1_P$1") (pintype "passive"))
      (node (ref "U1") (pin "24") (pinfunction "VREF_24") (pintype "bidirectional"))
    )
    (net (code "26") (name "Net-(C19-1)") (class "Default")
      (node (ref "C19") (pin "P$1") (pinfunction "1_P$1") (pintype "passive"))
      (node (ref "U1") (pin "19") (pinfunction "TEMP_19") (pintype "bidirectional"))
    )
    (net (code "27") (name "Net-(C20-1)") (class "Default")
      (node (ref "C20") (pin "P$1") (pinfunction "1_P$1") (pintype "passive"))
      (node (ref "U1") (pin "23") (pinfunction "VCOM_23") (pintype "bidirectional"))
    )
    (net (code "28") (name "Net-(C22-1)") (class "Default")
      (node (ref "C22") (pin "P$1") (pinfunction "1_P$1") (pintype "passive"))
      (node (ref "C23") (pin "P$1") (pinfunction "1_P$1") (pintype "passive"))
      (node (ref "L14") (pin "P$1") (pinfunction "1_P$1") (pintype "passive"))
      (node (ref "U$3") (pin "P$1") (pinfunction "VCC_P$1") (pintype "bidirectional"))
    )
    (net (code "29") (name "Net-(C26-1)") (class "Default")
      (node (ref "C26") (pin "P$1") (pinfunction "1_P$1") (pintype "passive"))
      (node (ref "L2") (pin "2") (pinfunction "P$2_2") (pintype "passive"))
      (node (ref "R23") (pin "P$2") (pinfunction "2_P$2") (pintype "passive"))
    )
    (net (code "30") (name "Net-(C26-2)") (class "Default")
      (node (ref "C26") (pin "P$2") (pinfunction "2_P$2") (pintype "passive"))
      (node (ref "L4") (pin "P$1") (pinfunction "1_P$1") (pintype "passive"))
    )
    (net (code "31") (name "Net-(C30-1)") (class "Default")
      (node (ref "C30") (pin "P$1") (pinfunction "1_P$1") (pintype "passive"))
      (node (ref "C6") (pin "P$1") (pinfunction "1_P$1") (pintype "passive"))
      (node (ref "L8") (pin "P$2") (pinfunction "2_P$2") (pintype "passive"))
      (node (ref "U1") (pin "28") (pinfunction "DVDD_28") (pintype "bidirectional"))
    )
    (net (code "32") (name "Net-(C31-1)") (class "Default")
      (node (ref "C31") (pin "P$1") (pinfunction "1_P$1") (pintype "passive"))
      (node (ref "C8") (pin "P$1") (pinfunction "1_P$1") (pintype "passive"))
      (node (ref "L6") (pin "P$2") (pinfunction "2_P$2") (pintype "passive"))
      (node (ref "U1") (pin "6") (pinfunction "VP_6") (pintype "bidirectional"))
    )
    (net (code "33") (name "Net-(C32-1)") (class "Default")
      (node (ref "C32") (pin "P$1") (pinfunction "1_P$1") (pintype "passive"))
      (node (ref "L11") (pin "P$1") (pinfunction "1_P$1") (pintype "passive"))
      (node (ref "R22") (pin "P$1") (pinfunction "1_P$1") (pintype "passive"))
      (node (ref "U2") (pin "1") (pinfunction "VIN_1") (pintype "power_in"))
    )
    (net (code "34") (name "Net-(C35-1)") (class "Default")
      (node (ref "C35") (pin "P$1") (pinfunction "1_P$1") (pintype "passive"))
      (node (ref "L3") (pin "1") (pinfunction "P$1_1") (pintype "passive"))
      (node (ref "R27") (pin "P$2") (pinfunction "2_P$2") (pintype "passive"))
    )
    (net (code "35") (name "Net-(C35-2)") (class "Default")
      (node (ref "C35") (pin "P$2") (pinfunction "2_P$2") (pintype "passive"))
      (node (ref "L1") (pin "P$1") (pinfunction "1_P$1") (pintype "passive"))
    )
    (net (code "36") (name "Net-(D1-ANODE)") (class "Default")
      (node (ref "D1") (pin "2") (pinfunction "ANODE_2") (pintype "passive"))
      (node (ref "R11") (pin "P$1") (pinfunction "1_P$1") (pintype "passive"))
      (node (ref "R6") (pin "P$2") (pinfunction "2_P$2") (pintype "passive"))
      (node (ref "R7") (pin "P$1") (pinfunction "1_P$1") (pintype "passive"))
      (node (ref "R8") (pin "P$1") (pinfunction "1_P$1") (pintype "passive"))
    )
    (net (code "37") (name "Net-(D5-ANODE)") (class "Default")
      (node (ref "D5") (pin "2") (pinfunction "ANODE_2") (pintype "passive"))
      (node (ref "R38") (pin "P$1") (pinfunction "1_P$1") (pintype "passive"))
    )
    (net (code "38") (name "Net-(J1-SIG)") (class "Default")
      (node (ref "J1") (pin "P$1") (pinfunction "SIG_P$1") (pintype "bidirectional"))
      (node (ref "L4") (pin "P$2") (pinfunction "2_P$2") (pintype "passive"))
    )
    (net (code "39") (name "Net-(J2-SIG)") (class "Default")
      (node (ref "J2") (pin "P$1") (pinfunction "SIG_P$1") (pintype "bidirectional"))
      (node (ref "L1") (pin "P$2") (pinfunction "2_P$2") (pintype "passive"))
    )
    (net (code "40") (name "Net-(L13-1)") (class "Default")
      (node (ref "L13") (pin "P$1") (pinfunction "1_P$1") (pintype "passive"))
      (node (ref "U$1") (pin "VIN") (pinfunction "VIN_VIN") (pintype "bidirectional"))
    )
    (net (code "41") (name "Net-(R1-1)") (class "Default")
      (node (ref "R1") (pin "P$1") (pinfunction "1_P$1") (pintype "passive"))
      (node (ref "R4") (pin "P$2") (pinfunction "2_P$2") (pintype "passive"))
      (node (ref "R5") (pin "P$1") (pinfunction "1_P$1") (pintype "passive"))
    )
    (net (code "42") (name "Net-(R5-2)") (class "Default")
      (node (ref "R5") (pin "P$2") (pinfunction "2_P$2") (pintype "passive"))
      (node (ref "U1") (pin "5") (pinfunction "SW_5") (pintype "bidirectional"))
    )
    (net (code "43") (name "Net-(R10-2)") (class "Default")
      (node (ref "R10") (pin "P$2") (pinfunction "2_P$2") (pintype "passive"))
      (node (ref "U$3") (pin "P$2") (pinfunction "OUTPUT_P$2") (pintype "bidirectional"))
    )
    (net (code "44") (name "Net-(R12-2)") (class "Default")
      (node (ref "R12") (pin "P$2") (pinfunction "2_P$2") (pintype "passive"))
      (node (ref "U1") (pin "22") (pinfunction "RSET_22") (pintype "bidirectional"))
    )
    (net (code "45") (name "Net-(R22-2)") (class "Default")
      (node (ref "R22") (pin "P$2") (pinfunction "2_P$2") (pintype "passive"))
      (node (ref "R24") (pin "P$1") (pinfunction "1_P$1") (pintype "passive"))
      (node (ref "U2") (pin "3") (pinfunction "EN_3") (pintype "input"))
    )
    (net (code "46") (name "Net-(R23-1)") (class "Default")
      (node (ref "R23") (pin "P$1") (pinfunction "1_P$1") (pintype "passive"))
      (node (ref "U1") (pin "12") (pinfunction "RF_OUT_A+_12") (pintype "bidirectional"))
    )
    (net (code "47") (name "Net-(R25-1)") (class "Default")
      (node (ref "R25") (pin "P$1") (pinfunction "1_P$1") (pintype "passive"))
      (node (ref "R3") (pin "P$2") (pinfunction "2_P$2") (pintype "passive"))
      (node (ref "U3") (pin "3") (pinfunction "EN_3") (pintype "input"))
    )
    (net (code "48") (name "Net-(R27-1)") (class "Default")
      (node (ref "R27") (pin "P$1") (pinfunction "1_P$1") (pintype "passive"))
      (node (ref "U1") (pin "13") (pinfunction "RF_OUT_A-_13") (pintype "bidirectional"))
    )
    (net (code "49") (name "Net-(TRIGGER1-PadP$1)") (class "Default")
      (node (ref "TRIGGER1") (pin "P$1") (pinfunction "P$1_P$1") (pintype "bidirectional"))
      (node (ref "U$1") (pin "4/CANRX") (pinfunction "4/CANRX_4/CANRX") (pintype "bidirectional"))
    )
    (net (code "50") (name "Net-(TRIGGER2-PadP$1)") (class "Default")
      (node (ref "TRIGGER2") (pin "P$1") (pinfunction "P$1_P$1") (pintype "bidirectional"))
      (node (ref "U$1") (pin "6") (pinfunction "6_6") (pintype "bidirectional"))
    )
    (net (code "51") (name "VDD") (class "Default")
      (node (ref "C13") (pin "P$1") (pinfunction "1_P$1") (pintype "passive"))
      (node (ref "C16") (pin "P$1") (pinfunction "1_P$1") (pintype "passive"))
      (node (ref "C21") (pin "P$1") (pinfunction "1_P$1") (pintype "passive"))
      (node (ref "C34") (pin "P$1") (pinfunction "1_P$1") (pintype "passive"))
      (node (ref "C5") (pin "P$1") (pinfunction "1_P$1") (pintype "passive"))
      (node (ref "C69") (pin "P$1") (pinfunction "1_P$1") (pintype "passive"))
      (node (ref "C7") (pin "P$1") (pinfunction "1_P$1") (pintype "passive"))
      (node (ref "C9") (pin "P$1") (pinfunction "1_P$1") (pintype "passive"))
      (node (ref "L10") (pin "P$2") (pinfunction "2_P$2") (pintype "passive"))
      (node (ref "L14") (pin "P$2") (pinfunction "2_P$2") (pintype "passive"))
      (node (ref "L5") (pin "P$1") (pinfunction "1_P$1") (pintype "passive"))
      (node (ref "L6") (pin "P$1") (pinfunction "1_P$1") (pintype "passive"))
      (node (ref "L7") (pin "P$1") (pinfunction "1_P$1") (pintype "passive"))
      (node (ref "L8") (pin "P$1") (pinfunction "1_P$1") (pintype "passive"))
      (node (ref "L9") (pin "P$1") (pinfunction "1_P$1") (pintype "passive"))
      (node (ref "R11") (pin "P$2") (pinfunction "2_P$2") (pintype "passive"))
      (node (ref "R13") (pin "P$2") (pinfunction "2_P$2") (pintype "passive"))
      (node (ref "R18") (pin "P$1") (pinfunction "1_P$1") (pintype "passive"))
      (node (ref "R19") (pin "P$1") (pinfunction "1_P$1") (pintype "passive"))
      (node (ref "R38") (pin "P$2") (pinfunction "2_P$2") (pintype "passive"))
      (node (ref "U2") (pin "5") (pinfunction "VOUT_5") (pintype "power_in"))
      (node (ref "VDD") (pin "TP") (pinfunction "TP_TP") (pintype "input"))
    )
    (net (code "52") (name "unconnected-(535L250X2GT5-EOH-PadEOH@3)") (class "Default")
      (node (ref "535L250X2GT5") (pin "EOH@3") (pinfunction "EOH_EOH@3") (pintype "bidirectional"))
    )
    (net (code "53") (name "unconnected-(535L250X2GT5-NC-Pad2)") (class "Default")
      (node (ref "535L250X2GT5") (pin "2") (pinfunction "NC_2") (pintype "bidirectional"))
    )
    (net (code "54") (name "unconnected-(535L250X2GT5-NC-Pad5)") (class "Default")
      (node (ref "535L250X2GT5") (pin "5") (pinfunction "NC_5") (pintype "bidirectional"))
    )
    (net (code "55") (name "unconnected-(535L250X2GT5-NC-Pad8)") (class "Default")
      (node (ref "535L250X2GT5") (pin "8") (pinfunction "NC_8") (pintype "bidirectional"))
    )
    (net (code "56") (name "unconnected-(535L250X2GT5-NC-Pad10)") (class "Default")
      (node (ref "535L250X2GT5") (pin "10") (pinfunction "NC_10") (pintype "bidirectional"))
    )
    (net (code "57") (name "unconnected-(535L250X2GT5-VC-PadVC@1)") (class "Default")
      (node (ref "535L250X2GT5") (pin "VC@1") (pinfunction "VC_VC@1") (pintype "bidirectional"))
    )
    (net (code "58") (name "unconnected-(U$1-A21{slash}DAC0-Pad21{slash}DAC0)") (class "Default")
      (node (ref "U$1") (pin "21/DAC0") (pinfunction "A21/DAC0_21/DAC0") (pintype "bidirectional"))
    )
    (net (code "59") (name "unconnected-(U$1-Pad0{slash}RX)") (class "Default")
      (node (ref "U$1") (pin "0/RX") (pinfunction "0/RX_0/RX") (pintype "bidirectional"))
    )
    (net (code "60") (name "unconnected-(U$1-Pad1{slash}TX)") (class "Default")
      (node (ref "U$1") (pin "1/TX") (pinfunction "1/TX_1/TX") (pintype "bidirectional"))
    )
    (net (code "61") (name "unconnected-(U$1-Pad3V3)") (class "Default")
      (node (ref "U$1") (pin "3V3") (pinfunction "3V3_3V3") (pintype "bidirectional"))
    )
    (net (code "62") (name "unconnected-(U$1-Pad3V3_LO)") (class "Default")
      (node (ref "U$1") (pin "3V3_LO") (pinfunction "3V3_LO_3V3_LO") (pintype "bidirectional"))
    )
    (net (code "63") (name "unconnected-(U$1-Pad3{slash}CANTX)") (class "Default")
      (node (ref "U$1") (pin "3/CANTX") (pinfunction "3/CANTX_3/CANTX") (pintype "bidirectional"))
    )
    (net (code "64") (name "unconnected-(U$1-Pad5)") (class "Default")
      (node (ref "U$1") (pin "5") (pinfunction "5_5") (pintype "bidirectional"))
    )
    (net (code "65") (name "unconnected-(U$1-Pad7)") (class "Default")
      (node (ref "U$1") (pin "7") (pinfunction "7_7") (pintype "bidirectional"))
    )
    (net (code "66") (name "unconnected-(U$1-Pad9{slash}CS)") (class "Default")
      (node (ref "U$1") (pin "9/CS") (pinfunction "9/CS_9/CS") (pintype "bidirectional"))
    )
    (net (code "67") (name "unconnected-(U$1-Pad12{slash}MISO)") (class "Default")
      (node (ref "U$1") (pin "12/MISO") (pinfunction "12/MISO_12/MISO") (pintype "bidirectional"))
    )
    (net (code "68") (name "unconnected-(U$1-Pad14{slash}A0)") (class "Default")
      (node (ref "U$1") (pin "14/A0") (pinfunction "14/A0_14/A0") (pintype "bidirectional"))
    )
    (net (code "69") (name "unconnected-(U$1-Pad15{slash}A1)") (class "Default")
      (node (ref "U$1") (pin "15/A1") (pinfunction "15/A1_15/A1") (pintype "bidirectional"))
    )
    (net (code "70") (name "unconnected-(U$1-Pad16{slash}A2)") (class "Default")
      (node (ref "U$1") (pin "16/A2") (pinfunction "16/A2_16/A2") (pintype "bidirectional"))
    )
    (net (code "71") (name "unconnected-(U$1-Pad17{slash}A3)") (class "Default")
      (node (ref "U$1") (pin "17/A3") (pinfunction "17/A3_17/A3") (pintype "bidirectional"))
    )
    (net (code "72") (name "unconnected-(U$1-Pad18{slash}A4{slash}SDA)") (class "Default")
      (node (ref "U$1") (pin "18/A4/SDA") (pinfunction "18/A4/SDA_18/A4/SDA") (pintype "bidirectional"))
    )
    (net (code "73") (name "unconnected-(U$1-Pad19{slash}A5{slash}SCL)") (class "Default")
      (node (ref "U$1") (pin "19/A5/SCL") (pinfunction "19/A5/SCL_19/A5/SCL") (pintype "bidirectional"))
    )
    (net (code "74") (name "unconnected-(U$1-Pad20{slash}A6)") (class "Default")
      (node (ref "U$1") (pin "20/A6") (pinfunction "20/A6_20/A6") (pintype "bidirectional"))
    )
    (net (code "75") (name "unconnected-(U$1-Pad21{slash}A7)") (class "Default")
      (node (ref "U$1") (pin "21/A7") (pinfunction "21/A7_21/A7") (pintype "bidirectional"))
    )
    (net (code "76") (name "unconnected-(U$1-Pad22{slash}A8)") (class "Default")
      (node (ref "U$1") (pin "22/A8") (pinfunction "22/A8_22/A8") (pintype "bidirectional"))
    )
    (net (code "77") (name "unconnected-(U$1-Pad23{slash}A9)") (class "Default")
      (node (ref "U$1") (pin "23/A9") (pinfunction "23/A9_23/A9") (pintype "bidirectional"))
    )
    (net (code "78") (name "unconnected-(U$1-Pad24)") (class "Default")
      (node (ref "U$1") (pin "24") (pinfunction "24_24") (pintype "bidirectional"))
    )
    (net (code "79") (name "unconnected-(U$1-Pad25)") (class "Default")
      (node (ref "U$1") (pin "25") (pinfunction "25_25") (pintype "bidirectional"))
    )
    (net (code "80") (name "unconnected-(U$1-Pad26)") (class "Default")
      (node (ref "U$1") (pin "26") (pinfunction "26_26") (pintype "bidirectional"))
    )
    (net (code "81") (name "unconnected-(U$1-Pad27)") (class "Default")
      (node (ref "U$1") (pin "27") (pinfunction "27_27") (pintype "bidirectional"))
    )
    (net (code "82") (name "unconnected-(U$1-Pad28)") (class "Default")
      (node (ref "U$1") (pin "28") (pinfunction "28_28") (pintype "bidirectional"))
    )
    (net (code "83") (name "unconnected-(U$1-Pad29)") (class "Default")
      (node (ref "U$1") (pin "29") (pinfunction "29_29") (pintype "bidirectional"))
    )
    (net (code "84") (name "unconnected-(U$1-Pad30)") (class "Default")
      (node (ref "U$1") (pin "30") (pinfunction "30_30") (pintype "bidirectional"))
    )
    (net (code "85") (name "unconnected-(U$1-Pad31{slash}A12)") (class "Default")
      (node (ref "U$1") (pin "31/A12") (pinfunction "31/A12_31/A12") (pintype "bidirectional"))
    )
    (net (code "86") (name "unconnected-(U$1-Pad32{slash}A13)") (class "Default")
      (node (ref "U$1") (pin "32/A13") (pinfunction "32/A13_32/A13") (pintype "bidirectional"))
    )
    (net (code "87") (name "unconnected-(U$1-Pad33{slash}A14)") (class "Default")
      (node (ref "U$1") (pin "33/A14") (pinfunction "33/A14_33/A14") (pintype "bidirectional"))
    )
    (net (code "88") (name "unconnected-(U$1-Pad34{slash}A15)") (class "Default")
      (node (ref "U$1") (pin "34/A15") (pinfunction "34/A15_34/A15") (pintype "bidirectional"))
    )
    (net (code "89") (name "unconnected-(U$1-Pad35{slash}A16)") (class "Default")
      (node (ref "U$1") (pin "35/A16") (pinfunction "35/A16_35/A16") (pintype "bidirectional"))
    )
    (net (code "90") (name "unconnected-(U$1-Pad36{slash}A17)") (class "Default")
      (node (ref "U$1") (pin "36/A17") (pinfunction "36/A17_36/A17") (pintype "bidirectional"))
    )
    (net (code "91") (name "unconnected-(U$1-Pad37{slash}A18)") (class "Default")
      (node (ref "U$1") (pin "37/A18") (pinfunction "37/A18_37/A18") (pintype "bidirectional"))
    )
    (net (code "92") (name "unconnected-(U$1-Pad38{slash}A19)") (class "Default")
      (node (ref "U$1") (pin "38/A19") (pinfunction "38/A19_38/A19") (pintype "bidirectional"))
    )
    (net (code "93") (name "unconnected-(U$1-PadA10)") (class "Default")
      (node (ref "U$1") (pin "A10") (pinfunction "A10_A10") (pintype "bidirectional"))
    )
    (net (code "94") (name "unconnected-(U$1-PadA11)") (class "Default")
      (node (ref "U$1") (pin "A11") (pinfunction "A11_A11") (pintype "bidirectional"))
    )
    (net (code "95") (name "unconnected-(U$1-PadA22{slash}DAC1)") (class "Default")
      (node (ref "U$1") (pin "A22/DAC1") (pinfunction "A22/DAC1_A22/DAC1") (pintype "bidirectional"))
    )
    (net (code "96") (name "unconnected-(U$1-PadAREF)") (class "Default")
      (node (ref "U$1") (pin "AREF") (pinfunction "AREF_AREF") (pintype "bidirectional"))
    )
    (net (code "97") (name "unconnected-(U$1-PadVUSB)") (class "Default")
      (node (ref "U$1") (pin "VUSB") (pinfunction "VUSB_VUSB") (pintype "bidirectional"))
    )
    (net (code "98") (name "unconnected-(U1-RF_OUT_B+-Pad14)") (class "Default")
      (node (ref "U1") (pin "14") (pinfunction "RF_OUT_B+_14") (pintype "bidirectional"))
    )
    (net (code "99") (name "unconnected-(U1-RF_OUT_B--Pad15)") (class "Default")
      (node (ref "U1") (pin "15") (pinfunction "RF_OUT_B-_15") (pintype "bidirectional"))
    )
    (net (code "100") (name "unconnected-(U2-NC-Pad4)") (class "Default")
      (node (ref "U2") (pin "4") (pinfunction "NC_4") (pintype "passive"))
    )
    (net (code "101") (name "unconnected-(U3-NC-Pad4)") (class "Default")
      (node (ref "U3") (pin "4") (pinfunction "NC_4") (pintype "passive"))
    )
  )
)
